# BatGPSTracker.net
KiCad netlist of a schematic drawn in Altium Designer
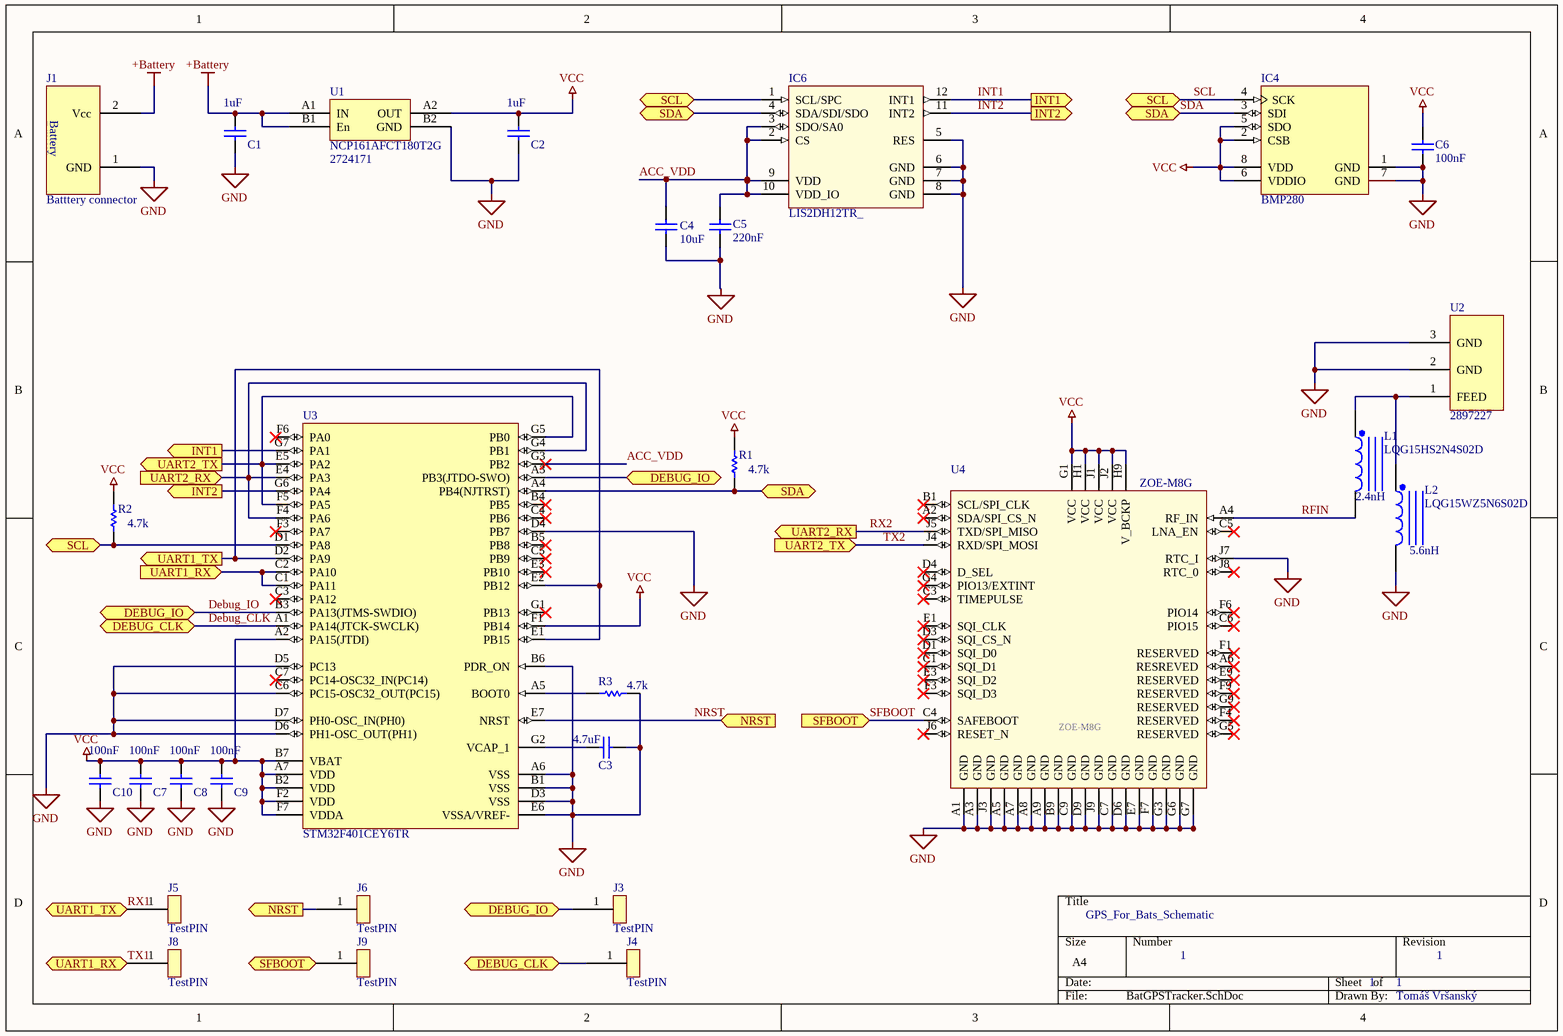
[diagram p0: BatGPSTracker.SchDoc]

(export (version "E")
  (design (tool "Eeschema 10.0.6"))
  (components
    (comp (ref "C1")
      (value "1uF")
      (footprint "CAPC0402(1005)60_L")
      (description "CAP 1uF 10V -20% to +80% 0402 (1005 Metric) Thickness 0.6mm SMD")
      (fields (field (name "TOLERANCE") "-20% to +80%") (field (name "Comment") "CAP 1uF 10V 0402(1005)"))
      (libsource (lib "Altium Content Vault") (part "CAP"))
    )
    (comp (ref "C2")
      (value "1uF")
      (footprint "CAPC0402(1005)60_L")
      (description "CAP 1uF 10V -20% to +80% 0402 (1005 Metric) Thickness 0.6mm SMD")
      (fields (field (name "TOLERANCE") "-20% to +80%") (field (name "Comment") "CAP 1uF 10V 0402(1005)"))
      (libsource (lib "Altium Content Vault") (part "CAP"))
    )
    (comp (ref "C3")
      (value "4.7uF")
      (footprint "CAPC0402(1005)60_L")
      (description "CAP 4.7uF 16V ±20% 0402 (1005 Metric) Thickness 0.6mm SMD")
      (fields (field (name "TOLERANCE") "Â±20%") (field (name "Comment") "CAP 4.7uF 16V 0402(1005)"))
      (libsource (lib "Altium Content Vault") (part "CMP-1034-01811-1"))
    )
    (comp (ref "C4")
      (value "10uF")
      (footprint "CAPC0402(1005)60_L")
      (description "CAP 10uF 6.3V ±20% 0402 (1005 Metric) Thickness 0.6mm SMD")
      (fields (field (name "TOLERANCE") "Â±20%") (field (name "Comment") "CAP 10uF 6.3V 0402(1005)"))
      (libsource (lib "Altium Content Vault") (part "CMP-1034-02138-1"))
    )
    (comp (ref "C5")
      (value "220nF")
      (footprint "CAPC0402(1005)60_L")
      (description "CAP 220nF 6.3V -20% to +80% 0402 (1005 Metric) Thickness 0.6mm SMD")
      (fields (field (name "TOLERANCE") "-20% to +80%") (field (name "Comment") "CAP 220nF 6.3V 0402(1005)"))
      (libsource (lib "Altium Content Vault") (part "CMP-1034-02085-1"))
    )
    (comp (ref "C6")
      (value "100nF")
      (footprint "CAPC0402(1005)60_L")
      (description "CAP 100nF 25V ±20% 0402 (1005 Metric) Thickness 0.6mm SMD")
      (fields (field (name "TOLERANCE") "Â±20%") (field (name "Comment") "CAP 100nF 25V 0402(1005)"))
      (libsource (lib "Altium Content Vault") (part "CMP-1034-02073-1"))
    )
    (comp (ref "C7")
      (value "100nF")
      (footprint "CAPC0402(1005)60_L")
      (description "CAP 1uF 10V -20% to +80% 0402 (1005 Metric) Thickness 0.6mm SMD")
      (fields (field (name "TOLERANCE") "-20% to +80%") (field (name "Comment") "CAP 100nF 10V 0402(1005)"))
      (libsource (lib "Altium Content Vault") (part "CAP"))
    )
    (comp (ref "C8")
      (value "100nF")
      (footprint "CAPC0402(1005)60_L")
      (description "CAP 1uF 10V -20% to +80% 0402 (1005 Metric) Thickness 0.6mm SMD")
      (fields (field (name "TOLERANCE") "-20% to +80%") (field (name "Comment") "CAP 100nF 10V 0402(1005)"))
      (libsource (lib "Altium Content Vault") (part "CAP"))
    )
    (comp (ref "C9")
      (value "100nF")
      (footprint "CAPC0402(1005)60_L")
      (description "CAP 1uF 10V -20% to +80% 0402 (1005 Metric) Thickness 0.6mm SMD")
      (fields (field (name "TOLERANCE") "-20% to +80%") (field (name "Comment") "CAP 100nF 10V 0402(1005)"))
      (libsource (lib "Altium Content Vault") (part "CAP"))
    )
    (comp (ref "C10")
      (value "100nF")
      (footprint "CAPC0402(1005)60_L")
      (description "CAP 1uF 10V -20% to +80% 0402 (1005 Metric) Thickness 0.6mm SMD")
      (fields (field (name "TOLERANCE") "-20% to +80%") (field (name "Comment") "CAP 100nF 10V 0402(1005)"))
      (libsource (lib "Altium Content Vault") (part "CAP"))
    )
    (comp (ref "IC4")
      (value "BMP280")
      (footprint "BOSC-LGA-8_V")
      (description "Digital Pressure Sensor, 1.71 to 3.6 V, -40 to 85 degC, 8-Pin LGA, RoHS, Tape and Reel")
      (fields (field (name "MANUFACTURER") "Bosch Sensortec"))
      (libsource (lib "Altium Content Vault") (part "CMP-2000-05076-1"))
    )
    (comp (ref "IC6")
      (value "LIS2DH12TR_")
      (footprint "LGA-12_")
      (libsource (lib "AerobTecL") (part "LIS2DH12TR_"))
    )
    (comp (ref "J1")
      (value "Batttery connector")
      (footprint "PCBCOMPONENT_1")
      (libsource (lib "Battery100mAh") (part "Component_1"))
    )
    (comp (ref "J3") (value "TestPIN") (libsource (lib "DebugPin") (part "Component_1")))
    (comp (ref "J4") (value "TestPIN") (libsource (lib "DebugPin") (part "Component_1")))
    (comp (ref "J5") (value "TestPIN") (libsource (lib "DebugPin") (part "Component_1")))
    (comp (ref "J6") (value "TestPIN") (libsource (lib "DebugPin") (part "Component_1")))
    (comp (ref "J8") (value "TestPIN") (libsource (lib "DebugPin") (part "Component_1")))
    (comp (ref "J9") (value "TestPIN") (libsource (lib "DebugPin") (part "Component_1")))
    (comp (ref "L1")
      (value "LQG15HS2N4S02D")
      (footprint "INDC1005X55X25ML05T10_A")
      (fields
        (field (name "INDUCTANCE") "2.4nH")
        (field (name "MANUFACTURER") "MurataElectronics")
        (field (name "TOLERANCE") "0.3nH")
      )
      (libsource (lib "Altium Content Vault") (part "IND-DOT-2"))
    )
    (comp (ref "L2")
      (value "LQG15WZ5N6S02D")
      (footprint "INDC1005X55X25ML05T10_A")
      (fields
        (field (name "INDUCTANCE") "5.6nH")
        (field (name "MANUFACTURER") "MurataElectronics")
        (field (name "TOLERANCE") "0.3nH")
      )
      (libsource (lib "Altium Content Vault") (part "CMP-2000-06579-1"))
    )
    (comp (ref "R1")
      (value "RMCF0402JT4K70")
      (footprint "RESC1005X40X25LL10T15")
      (description "Chip Resistor, 4.7 KOhm, +/- 5%, 0.063 W, -55 to 155 degC, 0402 (1005 Metric), RoHS, Tape and Reel")
      (fields
        (field (name "MANUFACTURER") "Stackpole-Electronics-Inc.")
        (field (name "TOLERANCE") "±5%")
        (field (name "RESISTANCE (OHMS)") "4.7k")
      )
      (libsource (lib "Altium Content Vault") (part "RES-2"))
    )
    (comp (ref "R2")
      (value "RMCF0402JT4K70")
      (footprint "RESC1005X40X25LL10T15")
      (description "Chip Resistor, 4.7 KOhm, +/- 5%, 0.063 W, -55 to 155 degC, 0402 (1005 Metric), RoHS, Tape and Reel")
      (fields
        (field (name "MANUFACTURER") "Stackpole-Electronics-Inc.")
        (field (name "TOLERANCE") "±5%")
        (field (name "RESISTANCE (OHMS)") "4.7k")
      )
      (libsource (lib "Altium Content Vault") (part "RES-2"))
    )
    (comp (ref "R3")
      (value "RMCF0402JT4K70")
      (footprint "RESC1005X40X25LL10T15")
      (description "Chip Resistor, 4.7 KOhm, +/- 5%, 0.063 W, -55 to 155 degC, 0402 (1005 Metric), RoHS, Tape and Reel")
      (fields
        (field (name "MANUFACTURER") "Stackpole-Electronics-Inc.")
        (field (name "TOLERANCE") "±5%")
        (field (name "RESISTANCE (OHMS)") "4.7k")
      )
      (libsource (lib "Altium Content Vault") (part "RES-2"))
    )
    (comp (ref "U1")
      (value "NCP161AFCT180T2G")
      (footprint "BGA4C40P2X2_84X84X60N")
      (description "1.8V Regulator")
      (fields (field (name "SUPPLIER PART NUMBER 1") "2724171"))
      (libsource (lib "NCP16") (part "Component_1"))
    )
    (comp (ref "U2")
      (value "W3011")
      (footprint "W3011")
      (description "GPS Chip antenna")
      (fields (field (name "SUPPLIER PART NUMBER 1") "2897227"))
      (libsource (lib "W3011") (part "Component_1"))
    )
    (comp (ref "U3")
      (value "STM32F401CEY6TR")
      (footprint "STM-WLCSP49-3060X3060DE_V")
      (libsource (lib "Altium Content Vault") (part "CMP-0243-00142-1"))
    )
    (comp (ref "U4")
      (value "ZOE-M8G")
      (footprint "ZOE-M8_ZOE-M8G(Primary)")
      (description "M8 Concurrent Gnss Module")
      (fields (field (name "MF") "u-blox"))
      (libsource (lib "ZOE-M8G") (part "ZOE-M8G"))
    )
  )
  (nets
    (net (code "1") (name "+Battery") (class "Default")
      (node (ref "C1") (pin "2") (pinfunction "2_2") (pintype "passive"))
      (node (ref "J1") (pin "2") (pinfunction "Vcc_2") (pintype "passive"))
      (node (ref "U1") (pin "A1") (pinfunction "IN_A1") (pintype "passive"))
      (node (ref "U1") (pin "B1") (pinfunction "En_B1") (pintype "passive"))
    )
    (net (code "2") (name "/ACC_VDD") (class "Default")
      (node (ref "C4") (pin "2") (pinfunction "2_2") (pintype "passive"))
      (node (ref "C5") (pin "2") (pinfunction "2_2") (pintype "passive"))
      (node (ref "IC6") (pin "10") (pinfunction "VDD_IO_10") (pintype "power_in"))
      (node (ref "IC6") (pin "2") (pinfunction "CS_2") (pintype "input"))
      (node (ref "IC6") (pin "3") (pinfunction "SDO/SA0_3") (pintype "bidirectional"))
      (node (ref "IC6") (pin "9") (pinfunction "VDD_9") (pintype "power_in"))
      (node (ref "U3") (pin "G3") (pinfunction "PB2_G3") (pintype "bidirectional"))
    )
    (net (code "3") (name "/Debug_CLK") (class "Default")
      (node (ref "J4") (pin "1") (pintype "passive"))
      (node (ref "U3") (pin "A1") (pinfunction "PA14(JTCK-SWCLK)_A1") (pintype "bidirectional"))
    )
    (net (code "4") (name "/Debug_IO") (class "Default")
      (node (ref "J3") (pin "1") (pintype "passive"))
      (node (ref "U3") (pin "A3") (pinfunction "PB3(JTDO-SWO)_A3") (pintype "bidirectional"))
      (node (ref "U3") (pin "B3") (pinfunction "PA13(JTMS-SWDIO)_B3") (pintype "bidirectional"))
    )
    (net (code "5") (name "/INT1") (class "Default")
      (node (ref "IC6") (pin "12") (pinfunction "INT1_12") (pintype "output"))
      (node (ref "U3") (pin "G7") (pinfunction "PA1_G7") (pintype "bidirectional"))
    )
    (net (code "6") (name "/INT2") (class "Default")
      (node (ref "IC6") (pin "11") (pinfunction "INT2_11") (pintype "output"))
      (node (ref "U3") (pin "G6") (pinfunction "PA4_G6") (pintype "bidirectional"))
    )
    (net (code "7") (name "/NRST") (class "Default")
      (node (ref "J6") (pin "1") (pintype "passive"))
      (node (ref "U3") (pin "E7") (pinfunction "NRST_E7") (pintype "bidirectional"))
    )
    (net (code "8") (name "/RFIN") (class "Default")
      (node (ref "L1") (pin "2") (pinfunction "2_2") (pintype "passive"))
      (node (ref "U4") (pin "A4") (pinfunction "RF_IN_A4") (pintype "input"))
    )
    (net (code "9") (name "/RX1") (class "Default")
      (node (ref "J5") (pin "1") (pintype "passive"))
      (node (ref "U3") (pin "D2") (pinfunction "PA9_D2") (pintype "bidirectional"))
      (node (ref "U3") (pin "E1") (pinfunction "PB15_E1") (pintype "bidirectional"))
      (node (ref "U3") (pin "E2") (pinfunction "PB12_E2") (pintype "bidirectional"))
    )
    (net (code "10") (name "/RX2") (class "Default")
      (node (ref "U3") (pin "E4") (pinfunction "PA3_E4") (pintype "bidirectional"))
      (node (ref "U3") (pin "F4") (pinfunction "PA6_F4") (pintype "bidirectional"))
      (node (ref "U3") (pin "G4") (pinfunction "PB1_G4") (pintype "bidirectional"))
      (node (ref "U4") (pin "J5") (pinfunction "TXD/SPI_MISO_J5") (pintype "bidirectional"))
    )
    (net (code "11") (name "/SCL") (class "Default")
      (node (ref "IC4") (pin "4") (pinfunction "SCK_4") (pintype "input"))
      (node (ref "IC6") (pin "1") (pinfunction "SCL/SPC_1") (pintype "input"))
      (node (ref "R2") (pin "1") (pinfunction "1_1") (pintype "passive"))
      (node (ref "U3") (pin "D1") (pinfunction "PA8_D1") (pintype "bidirectional"))
    )
    (net (code "12") (name "/SDA") (class "Default")
      (node (ref "IC4") (pin "3") (pinfunction "SDI_3") (pintype "bidirectional"))
      (node (ref "IC6") (pin "4") (pinfunction "SDA/SDI/SDO_4") (pintype "bidirectional"))
      (node (ref "R1") (pin "1") (pinfunction "1_1") (pintype "passive"))
      (node (ref "U3") (pin "A4") (pinfunction "PB4(NJTRST)_A4") (pintype "bidirectional"))
    )
    (net (code "13") (name "/SFBOOT") (class "Default")
      (node (ref "J9") (pin "1") (pintype "passive"))
      (node (ref "U4") (pin "C4") (pinfunction "SAFEBOOT_C4") (pintype "bidirectional"))
    )
    (net (code "14") (name "/TX1") (class "Default")
      (node (ref "J8") (pin "1") (pintype "passive"))
      (node (ref "U3") (pin "C1") (pinfunction "PA11_C1") (pintype "bidirectional"))
      (node (ref "U3") (pin "C2") (pinfunction "PA10_C2") (pintype "bidirectional"))
    )
    (net (code "15") (name "/TX2") (class "Default")
      (node (ref "U3") (pin "E5") (pinfunction "PA2_E5") (pintype "bidirectional"))
      (node (ref "U3") (pin "F5") (pinfunction "PA5_F5") (pintype "bidirectional"))
      (node (ref "U3") (pin "G5") (pinfunction "PB0_G5") (pintype "bidirectional"))
      (node (ref "U4") (pin "J4") (pinfunction "RXD/SPI_MOSI_J4") (pintype "bidirectional"))
    )
    (net (code "16") (name "GND") (class "Default")
      (node (ref "C1") (pin "1") (pinfunction "1_1") (pintype "passive"))
      (node (ref "C10") (pin "1") (pinfunction "1_1") (pintype "passive"))
      (node (ref "C2") (pin "1") (pinfunction "1_1") (pintype "passive"))
      (node (ref "C3") (pin "2") (pinfunction "2_2") (pintype "passive"))
      (node (ref "C4") (pin "1") (pinfunction "1_1") (pintype "passive"))
      (node (ref "C5") (pin "1") (pinfunction "1_1") (pintype "passive"))
      (node (ref "C6") (pin "1") (pinfunction "1_1") (pintype "passive"))
      (node (ref "C7") (pin "1") (pinfunction "1_1") (pintype "passive"))
      (node (ref "C8") (pin "1") (pinfunction "1_1") (pintype "passive"))
      (node (ref "C9") (pin "1") (pinfunction "1_1") (pintype "passive"))
      (node (ref "IC4") (pin "1") (pinfunction "GND_1") (pintype "power_in"))
      (node (ref "IC4") (pin "7") (pinfunction "GND_7") (pintype "power_in"))
      (node (ref "IC6") (pin "5") (pinfunction "RES_5") (pintype "passive"))
      (node (ref "IC6") (pin "6") (pinfunction "GND_6") (pintype "power_in"))
      (node (ref "IC6") (pin "7") (pinfunction "GND_7") (pintype "power_in"))
      (node (ref "IC6") (pin "8") (pinfunction "GND_8") (pintype "power_in"))
      (node (ref "J1") (pin "1") (pinfunction "GND_1") (pintype "passive"))
      (node (ref "L2") (pin "2") (pinfunction "2_2") (pintype "passive"))
      (node (ref "R3") (pin "1") (pinfunction "1_1") (pintype "passive"))
      (node (ref "U1") (pin "B2") (pinfunction "GND_B2") (pintype "passive"))
      (node (ref "U2") (pin "2") (pinfunction "GND_2") (pintype "passive"))
      (node (ref "U2") (pin "3") (pinfunction "GND_3") (pintype "passive"))
      (node (ref "U3") (pin "A6") (pinfunction "VSS_A6") (pintype "power_in"))
      (node (ref "U3") (pin "B1") (pinfunction "VSS_B1") (pintype "power_in"))
      (node (ref "U3") (pin "B6") (pinfunction "PDR_ON_B6") (pintype "input"))
      (node (ref "U3") (pin "C6") (pinfunction "PC15-OSC32_OUT(PC15)_C6") (pintype "bidirectional"))
      (node (ref "U3") (pin "D3") (pinfunction "VSS_D3") (pintype "power_in"))
      (node (ref "U3") (pin "D4") (pinfunction "PB7_D4") (pintype "bidirectional"))
      (node (ref "U3") (pin "D5") (pinfunction "PC13_D5") (pintype "bidirectional"))
      (node (ref "U3") (pin "D6") (pinfunction "PH1-OSC_OUT(PH1)_D6") (pintype "bidirectional"))
      (node (ref "U3") (pin "D7") (pinfunction "PH0-OSC_IN(PH0)_D7") (pintype "bidirectional"))
      (node (ref "U3") (pin "E6") (pinfunction "VSSA/VREF-_E6") (pintype "power_in"))
      (node (ref "U4") (pin "A1") (pinfunction "GND_A1") (pintype "power_in"))
      (node (ref "U4") (pin "A3") (pinfunction "GND_A3") (pintype "power_in"))
      (node (ref "U4") (pin "A5") (pinfunction "GND_A5") (pintype "power_in"))
      (node (ref "U4") (pin "A7") (pinfunction "GND_A7") (pintype "power_in"))
      (node (ref "U4") (pin "A8") (pinfunction "GND_A8") (pintype "power_in"))
      (node (ref "U4") (pin "A9") (pinfunction "GND_A9") (pintype "power_in"))
      (node (ref "U4") (pin "B9") (pinfunction "GND_B9") (pintype "power_in"))
      (node (ref "U4") (pin "C7") (pinfunction "GND_C7") (pintype "power_in"))
      (node (ref "U4") (pin "C9") (pinfunction "GND_C9") (pintype "power_in"))
      (node (ref "U4") (pin "D6") (pinfunction "GND_D6") (pintype "power_in"))
      (node (ref "U4") (pin "D9") (pinfunction "GND_D9") (pintype "power_in"))
      (node (ref "U4") (pin "E7") (pinfunction "GND_E7") (pintype "power_in"))
      (node (ref "U4") (pin "F7") (pinfunction "GND_F7") (pintype "power_in"))
      (node (ref "U4") (pin "G3") (pinfunction "GND_G3") (pintype "power_in"))
      (node (ref "U4") (pin "G6") (pinfunction "GND_G6") (pintype "power_in"))
      (node (ref "U4") (pin "G7") (pinfunction "GND_G7") (pintype "power_in"))
      (node (ref "U4") (pin "J3") (pinfunction "GND_J3") (pintype "power_in"))
      (node (ref "U4") (pin "J7") (pinfunction "RTC_I_J7") (pintype "bidirectional"))
      (node (ref "U4") (pin "J9") (pinfunction "GND_J9") (pintype "power_in"))
    )
    (net (code "17") (name "Net-(U2-FEED)") (class "Default")
      (node (ref "L1") (pin "1") (pinfunction "1_1") (pintype "passive"))
      (node (ref "L2") (pin "1") (pinfunction "1_1") (pintype "passive"))
      (node (ref "U2") (pin "1") (pinfunction "FEED_1") (pintype "passive"))
    )
    (net (code "18") (name "Net-(U3-BOOT0)") (class "Default")
      (node (ref "R3") (pin "2") (pinfunction "2_2") (pintype "passive"))
      (node (ref "U3") (pin "A5") (pinfunction "BOOT0_A5") (pintype "input"))
    )
    (net (code "19") (name "Net-(U3-VCAP_1)") (class "Default")
      (node (ref "C3") (pin "1") (pinfunction "1_1") (pintype "passive"))
      (node (ref "U3") (pin "G2") (pinfunction "VCAP_1_G2") (pintype "passive"))
    )
    (net (code "20") (name "VCC") (class "Default")
      (node (ref "C10") (pin "2") (pinfunction "2_2") (pintype "passive"))
      (node (ref "C2") (pin "2") (pinfunction "2_2") (pintype "passive"))
      (node (ref "C6") (pin "2") (pinfunction "2_2") (pintype "passive"))
      (node (ref "C7") (pin "2") (pinfunction "2_2") (pintype "passive"))
      (node (ref "C8") (pin "2") (pinfunction "2_2") (pintype "passive"))
      (node (ref "C9") (pin "2") (pinfunction "2_2") (pintype "passive"))
      (node (ref "IC4") (pin "2") (pinfunction "CSB_2") (pintype "input"))
      (node (ref "IC4") (pin "5") (pinfunction "SDO_5") (pintype "bidirectional"))
      (node (ref "IC4") (pin "6") (pinfunction "VDDIO_6") (pintype "power_in"))
      (node (ref "IC4") (pin "8") (pinfunction "VDD_8") (pintype "power_in"))
      (node (ref "R1") (pin "2") (pinfunction "2_2") (pintype "passive"))
      (node (ref "R2") (pin "2") (pinfunction "2_2") (pintype "passive"))
      (node (ref "U1") (pin "A2") (pinfunction "OUT_A2") (pintype "passive"))
      (node (ref "U3") (pin "A2") (pinfunction "PA15(JTDI)_A2") (pintype "bidirectional"))
      (node (ref "U3") (pin "A7") (pinfunction "VDD_A7") (pintype "power_in"))
      (node (ref "U3") (pin "B2") (pinfunction "VDD_B2") (pintype "power_in"))
      (node (ref "U3") (pin "B7") (pinfunction "VBAT_B7") (pintype "power_in"))
      (node (ref "U3") (pin "F1") (pinfunction "PB14_F1") (pintype "bidirectional"))
      (node (ref "U3") (pin "F2") (pinfunction "VDD_F2") (pintype "power_in"))
      (node (ref "U3") (pin "F7") (pinfunction "VDDA_F7") (pintype "power_in"))
      (node (ref "U4") (pin "G1") (pinfunction "VCC_G1") (pintype "power_in"))
      (node (ref "U4") (pin "H1") (pinfunction "VCC_H1") (pintype "power_in"))
      (node (ref "U4") (pin "H9") (pinfunction "V_BCKP_H9") (pintype "power_in"))
      (node (ref "U4") (pin "J1") (pinfunction "VCC_J1") (pintype "power_in"))
      (node (ref "U4") (pin "J2") (pinfunction "VCC_J2") (pintype "power_in"))
    )
    (net (code "21") (name "unconnected-(U3-PA0-PadF6)") (class "Default")
      (node (ref "U3") (pin "F6") (pinfunction "PA0_F6") (pintype "bidirectional+no_connect"))
    )
    (net (code "22") (name "unconnected-(U3-PA7-PadF3)") (class "Default")
      (node (ref "U3") (pin "F3") (pinfunction "PA7_F3") (pintype "bidirectional+no_connect"))
    )
    (net (code "23") (name "unconnected-(U3-PA12-PadC3)") (class "Default")
      (node (ref "U3") (pin "C3") (pinfunction "PA12_C3") (pintype "bidirectional+no_connect"))
    )
    (net (code "24") (name "unconnected-(U3-PB5-PadB4)") (class "Default")
      (node (ref "U3") (pin "B4") (pinfunction "PB5_B4") (pintype "bidirectional+no_connect"))
    )
    (net (code "25") (name "unconnected-(U3-PB6-PadC4)") (class "Default")
      (node (ref "U3") (pin "C4") (pinfunction "PB6_C4") (pintype "bidirectional+no_connect"))
    )
    (net (code "26") (name "unconnected-(U3-PB8-PadB5)") (class "Default")
      (node (ref "U3") (pin "B5") (pinfunction "PB8_B5") (pintype "bidirectional+no_connect"))
    )
    (net (code "27") (name "unconnected-(U3-PB9-PadC5)") (class "Default")
      (node (ref "U3") (pin "C5") (pinfunction "PB9_C5") (pintype "bidirectional+no_connect"))
    )
    (net (code "28") (name "unconnected-(U3-PB10-PadE3)") (class "Default")
      (node (ref "U3") (pin "E3") (pinfunction "PB10_E3") (pintype "bidirectional+no_connect"))
    )
    (net (code "29") (name "unconnected-(U3-PB13-PadG1)") (class "Default")
      (node (ref "U3") (pin "G1") (pinfunction "PB13_G1") (pintype "bidirectional+no_connect"))
    )
    (net (code "30") (name "unconnected-(U3-PC14-OSC32_IN(PC14)-PadC7)") (class "Default")
      (node (ref "U3") (pin "C7") (pinfunction "PC14-OSC32_IN(PC14)_C7") (pintype "bidirectional+no_connect"))
    )
    (net (code "31") (name "unconnected-(U4-D_SEL-PadD4)") (class "Default")
      (node (ref "U4") (pin "D4") (pinfunction "D_SEL_D4") (pintype "bidirectional+no_connect"))
    )
    (net (code "32") (name "unconnected-(U4-LNA_EN-PadC5)") (class "Default")
      (node (ref "U4") (pin "C5") (pinfunction "LNA_EN_C5") (pintype "bidirectional+no_connect"))
    )
    (net (code "33") (name "unconnected-(U4-PIO13{slash}EXTINT-PadG4)") (class "Default")
      (node (ref "U4") (pin "G4") (pinfunction "PIO13/EXTINT_G4") (pintype "bidirectional+no_connect"))
    )
    (net (code "34") (name "unconnected-(U4-PIO14-PadF6)") (class "Default")
      (node (ref "U4") (pin "F6") (pinfunction "PIO14_F6") (pintype "bidirectional+no_connect"))
    )
    (net (code "35") (name "unconnected-(U4-PIO15-PadC6)") (class "Default")
      (node (ref "U4") (pin "C6") (pinfunction "PIO15_C6") (pintype "bidirectional+no_connect"))
    )
    (net (code "36") (name "unconnected-(U4-RESERVED-PadE9)") (class "Default")
      (node (ref "U4") (pin "E9") (pinfunction "RESERVED_E9") (pintype "bidirectional+no_connect"))
    )
    (net (code "37") (name "unconnected-(U4-RESERVED-PadF1)") (class "Default")
      (node (ref "U4") (pin "F1") (pinfunction "RESERVED_F1") (pintype "bidirectional+no_connect"))
    )
    (net (code "38") (name "unconnected-(U4-RESERVED-PadF4)") (class "Default")
      (node (ref "U4") (pin "F4") (pinfunction "RESERVED_F4") (pintype "bidirectional+no_connect"))
    )
    (net (code "39") (name "unconnected-(U4-RESERVED-PadF9)") (class "Default")
      (node (ref "U4") (pin "F9") (pinfunction "RESERVED_F9") (pintype "bidirectional+no_connect"))
    )
    (net (code "40") (name "unconnected-(U4-RESERVED-PadG5)") (class "Default")
      (node (ref "U4") (pin "G5") (pinfunction "RESERVED_G5") (pintype "bidirectional+no_connect"))
    )
    (net (code "41") (name "unconnected-(U4-RESERVED-PadG9)") (class "Default")
      (node (ref "U4") (pin "G9") (pinfunction "RESERVED_G9") (pintype "bidirectional+no_connect"))
    )
    (net (code "42") (name "unconnected-(U4-RESET_N-PadJ6)") (class "Default")
      (node (ref "U4") (pin "J6") (pinfunction "RESET_N_J6") (pintype "bidirectional+no_connect"))
    )
    (net (code "43") (name "unconnected-(U4-RESREVED-PadA6)") (class "Default")
      (node (ref "U4") (pin "A6") (pinfunction "RESREVED_A6") (pintype "bidirectional+no_connect"))
    )
    (net (code "44") (name "unconnected-(U4-RTC_0-PadJ8)") (class "Default")
      (node (ref "U4") (pin "J8") (pinfunction "RTC_0_J8") (pintype "bidirectional+no_connect"))
    )
    (net (code "45") (name "unconnected-(U4-SCL{slash}SPI_CLK-PadB1)") (class "Default")
      (node (ref "U4") (pin "B1") (pinfunction "SCL/SPI_CLK_B1") (pintype "bidirectional+no_connect"))
    )
    (net (code "46") (name "unconnected-(U4-SDA{slash}SPI_CS_N-PadA2)") (class "Default")
      (node (ref "U4") (pin "A2") (pinfunction "SDA/SPI_CS_N_A2") (pintype "bidirectional+no_connect"))
    )
    (net (code "47") (name "unconnected-(U4-SQI_CLK-PadE1)") (class "Default")
      (node (ref "U4") (pin "E1") (pinfunction "SQI_CLK_E1") (pintype "bidirectional+no_connect"))
    )
    (net (code "48") (name "unconnected-(U4-SQI_CS_N-PadD3)") (class "Default")
      (node (ref "U4") (pin "D3") (pinfunction "SQI_CS_N_D3") (pintype "bidirectional+no_connect"))
    )
    (net (code "49") (name "unconnected-(U4-SQI_D0-PadD1)") (class "Default")
      (node (ref "U4") (pin "D1") (pinfunction "SQI_D0_D1") (pintype "bidirectional+no_connect"))
    )
    (net (code "50") (name "unconnected-(U4-SQI_D1-PadC1)") (class "Default")
      (node (ref "U4") (pin "C1") (pinfunction "SQI_D1_C1") (pintype "bidirectional+no_connect"))
    )
    (net (code "51") (name "unconnected-(U4-SQI_D2-PadE3)") (class "Default")
      (node (ref "U4") (pin "E3") (pinfunction "SQI_D2_E3") (pintype "bidirectional+no_connect"))
    )
    (net (code "52") (name "unconnected-(U4-SQI_D3-PadF3)") (class "Default")
      (node (ref "U4") (pin "F3") (pinfunction "SQI_D3_F3") (pintype "bidirectional+no_connect"))
    )
    (net (code "53") (name "unconnected-(U4-TIMEPULSE-PadC3)") (class "Default")
      (node (ref "U4") (pin "C3") (pinfunction "TIMEPULSE_C3") (pintype "bidirectional+no_connect"))
    )
  )
)
